# ECLOCK01.net
KiCad netlist of a schematic drawn in EAGLE
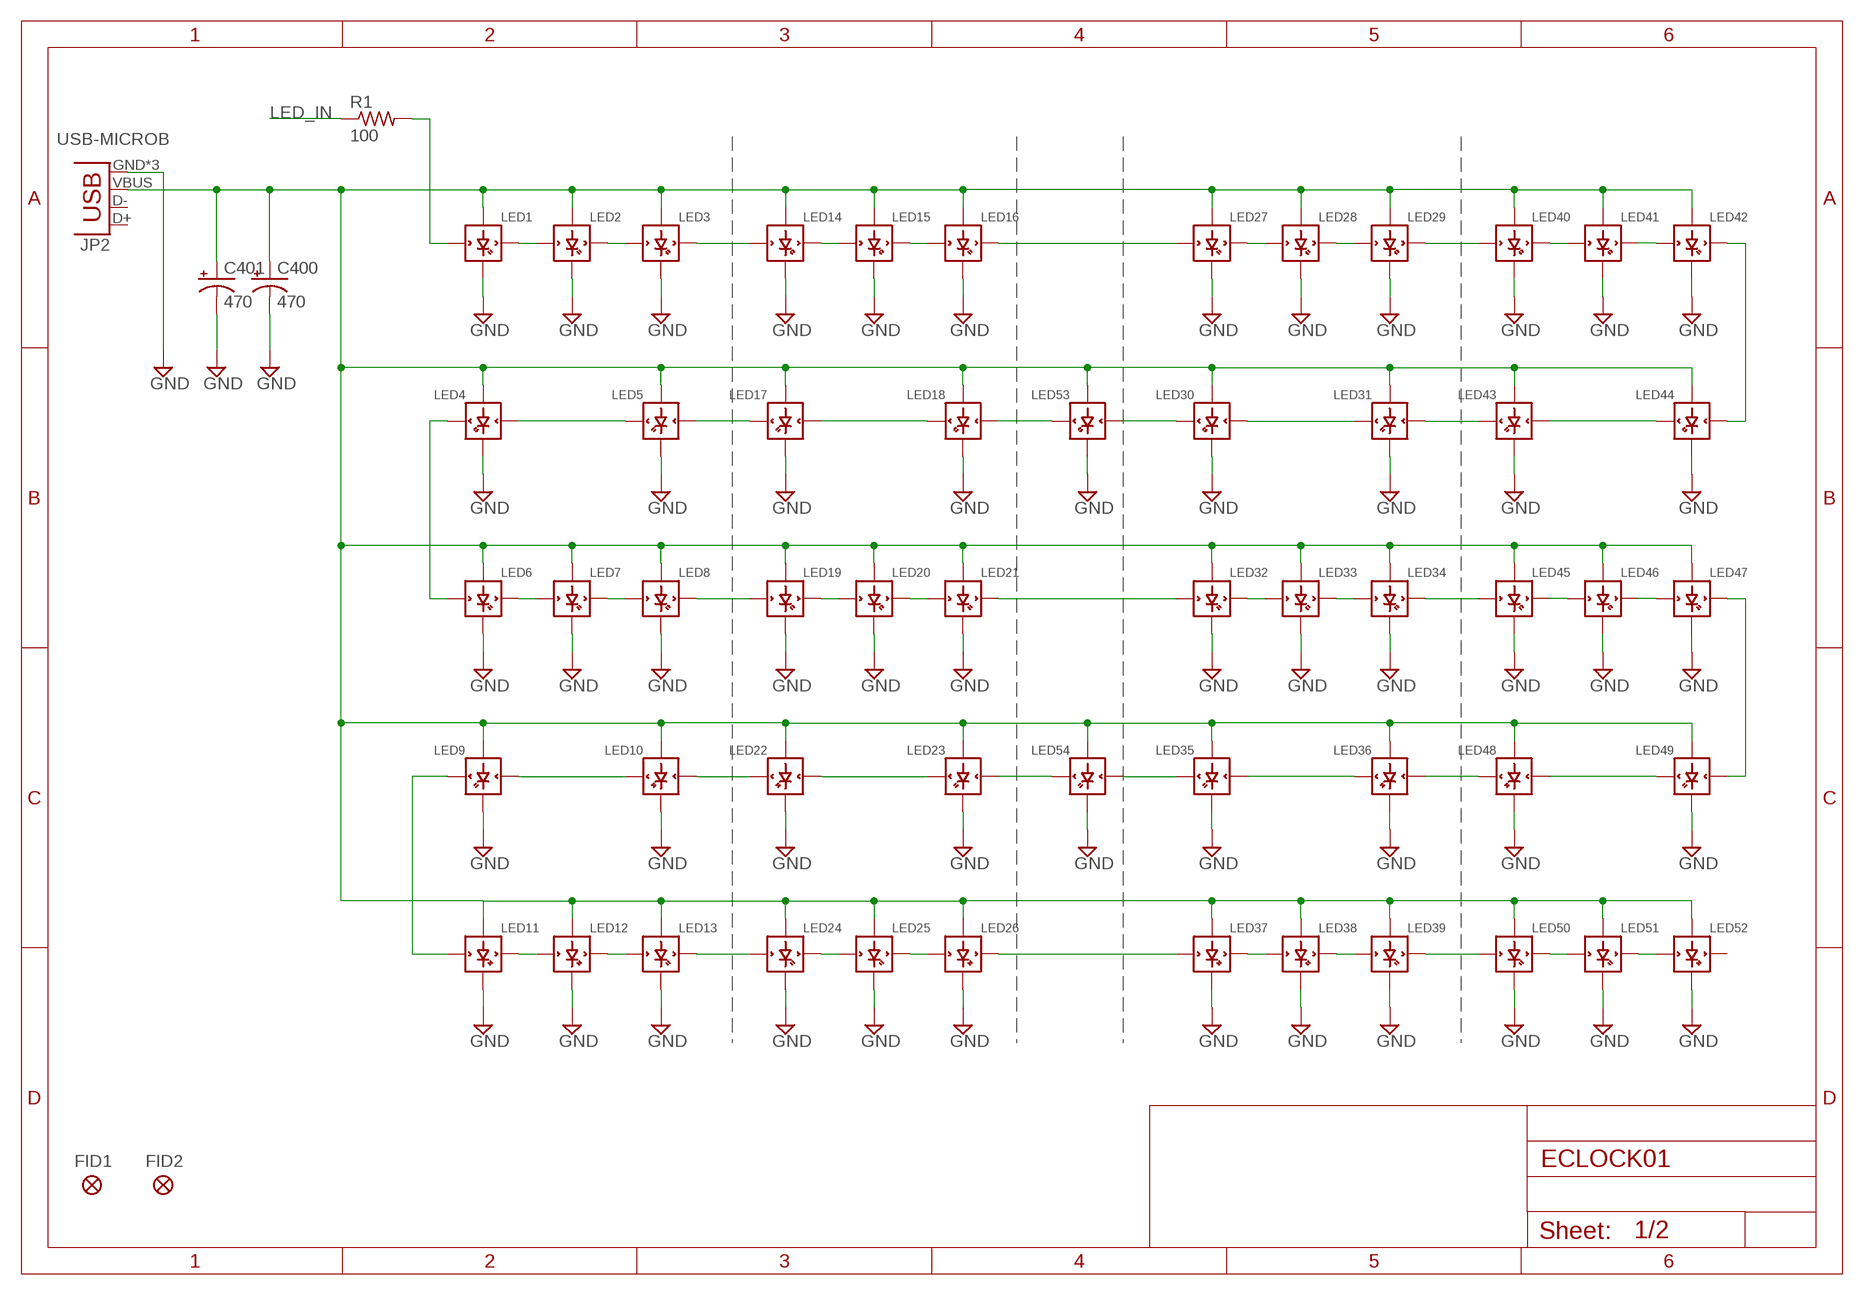
[diagram p0: schematic, sheet 1]
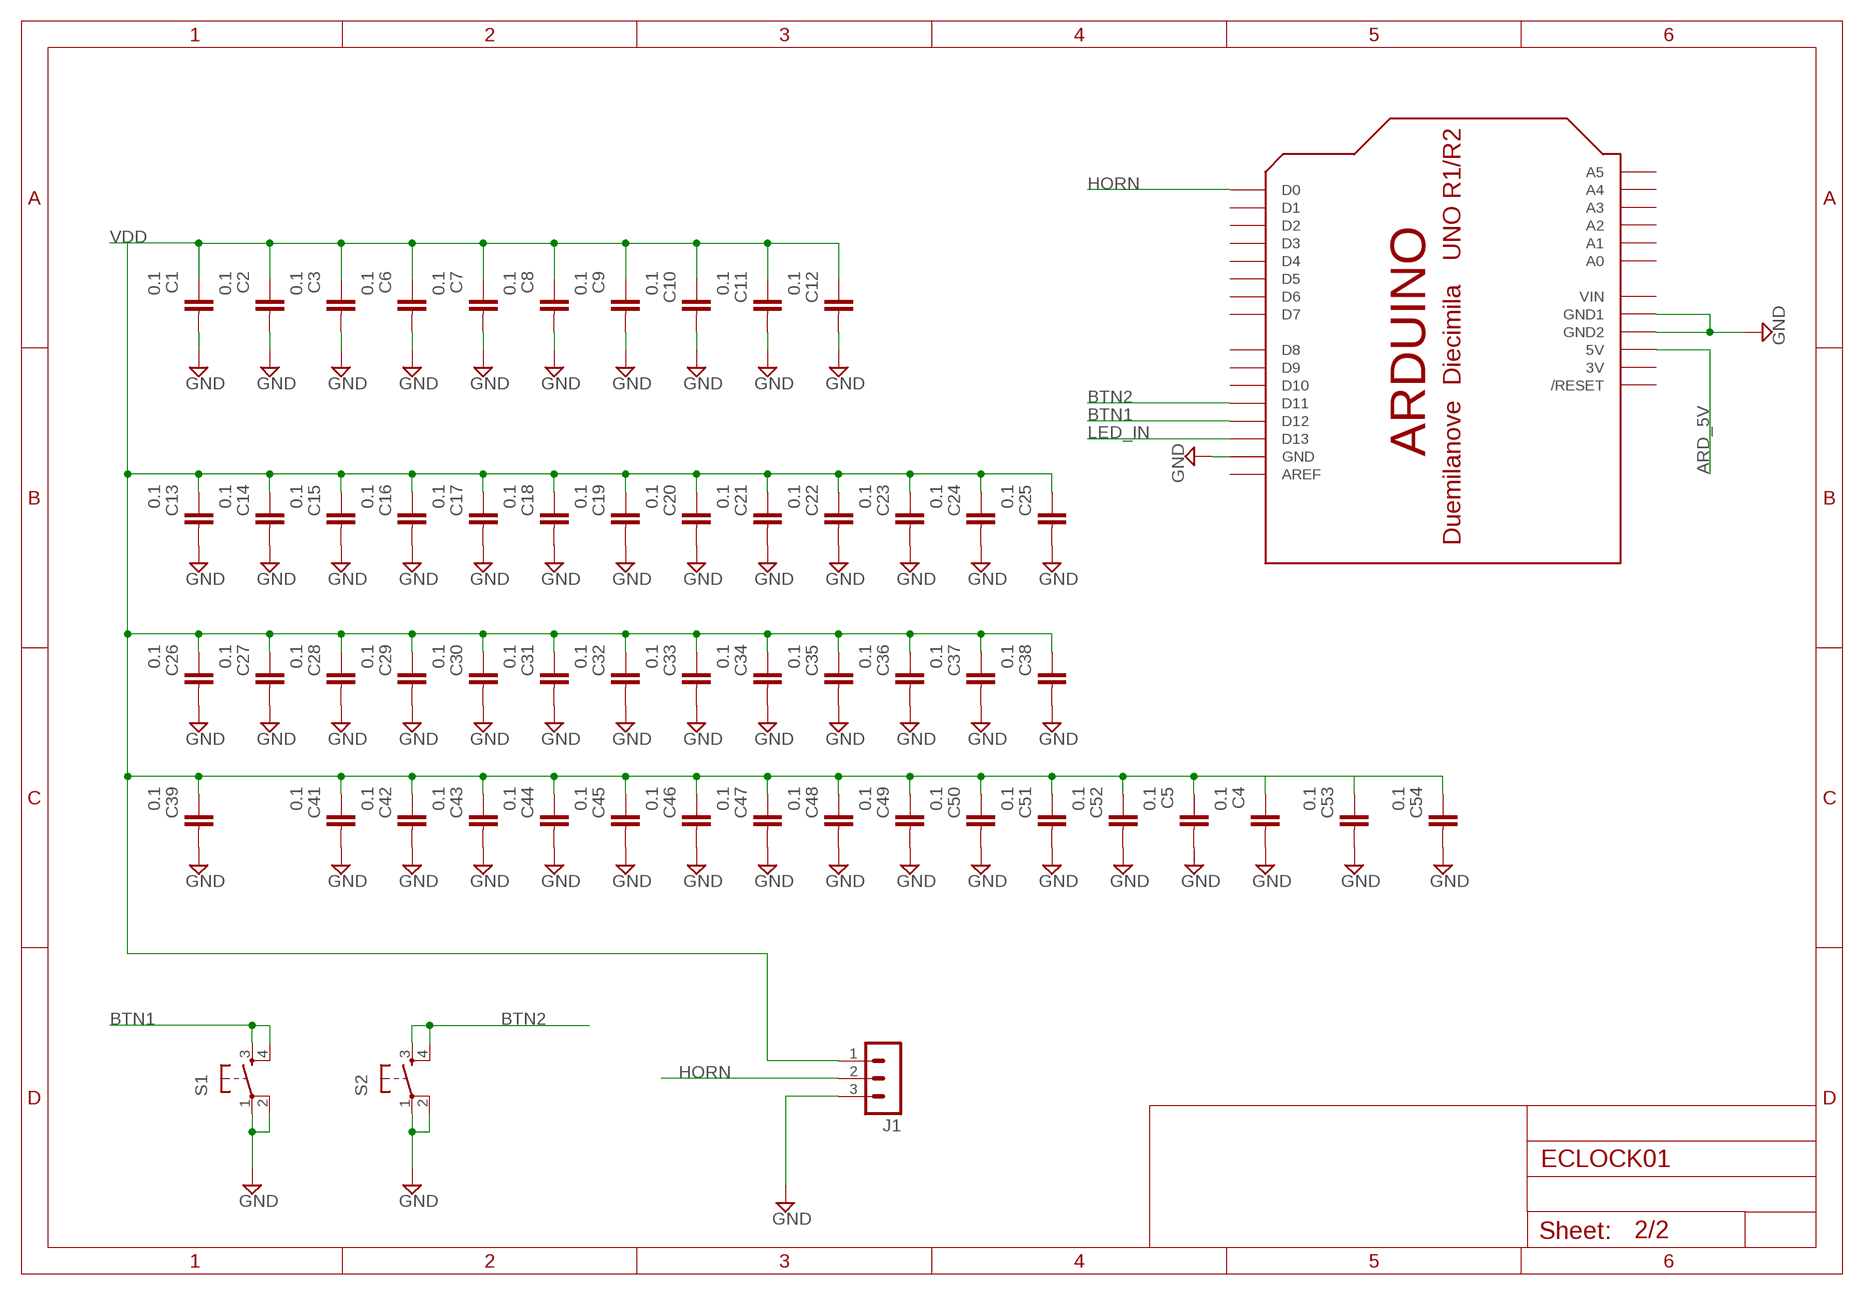
[diagram p1: schematic, sheet 2]

(export (version "E")
  (design (tool "Eeschema 10.0.6"))
  (components
    (comp (ref "C400")
      (value "470")
      (footprint "eagle-import:PANASONIC_E")
      (libsource (lib "eagle-import") (part "CPOL-USE"))
    )
    (comp (ref "C401")
      (value "470")
      (footprint "eagle-import:PANASONIC_E")
      (libsource (lib "eagle-import") (part "CPOL-USE"))
    )
    (comp (ref "FID1")
      (value "FIDUCIAL")
      (footprint "eagle-import:FIDUCIAL")
      (libsource (lib "eagle-import") (part "FIDUCIAL"))
    )
    (comp (ref "FID2")
      (value "FIDUCIAL")
      (footprint "eagle-import:FIDUCIAL")
      (libsource (lib "eagle-import") (part "FIDUCIAL"))
    )
    (comp (ref "JP2")
      (value "USB-MICROB")
      (footprint "eagle-import:USB-MICROB")
      (libsource (lib "eagle-import") (part "USB-MICROB"))
    )
    (comp (ref "LED1")
      (value "WS2812B")
      (footprint "eagle-import:WS2812B")
      (libsource (lib "eagle-import") (part "WS2812B"))
    )
    (comp (ref "LED2")
      (value "WS2812B")
      (footprint "eagle-import:WS2812B")
      (libsource (lib "eagle-import") (part "WS2812B"))
    )
    (comp (ref "LED3")
      (value "WS2812B")
      (footprint "eagle-import:WS2812B")
      (libsource (lib "eagle-import") (part "WS2812B"))
    )
    (comp (ref "LED4")
      (value "WS2812B")
      (footprint "eagle-import:WS2812B")
      (libsource (lib "eagle-import") (part "WS2812B"))
    )
    (comp (ref "LED5")
      (value "WS2812B")
      (footprint "eagle-import:WS2812B")
      (libsource (lib "eagle-import") (part "WS2812B"))
    )
    (comp (ref "LED6")
      (value "WS2812B")
      (footprint "eagle-import:WS2812B")
      (libsource (lib "eagle-import") (part "WS2812B"))
    )
    (comp (ref "LED7")
      (value "WS2812B")
      (footprint "eagle-import:WS2812B")
      (libsource (lib "eagle-import") (part "WS2812B"))
    )
    (comp (ref "LED8")
      (value "WS2812B")
      (footprint "eagle-import:WS2812B")
      (libsource (lib "eagle-import") (part "WS2812B"))
    )
    (comp (ref "LED9")
      (value "WS2812B")
      (footprint "eagle-import:WS2812B")
      (libsource (lib "eagle-import") (part "WS2812B"))
    )
    (comp (ref "LED10")
      (value "WS2812B")
      (footprint "eagle-import:WS2812B")
      (libsource (lib "eagle-import") (part "WS2812B"))
    )
    (comp (ref "LED11")
      (value "WS2812B")
      (footprint "eagle-import:WS2812B")
      (libsource (lib "eagle-import") (part "WS2812B"))
    )
    (comp (ref "LED12")
      (value "WS2812B")
      (footprint "eagle-import:WS2812B")
      (libsource (lib "eagle-import") (part "WS2812B"))
    )
    (comp (ref "LED13")
      (value "WS2812B")
      (footprint "eagle-import:WS2812B")
      (libsource (lib "eagle-import") (part "WS2812B"))
    )
    (comp (ref "LED14")
      (value "WS2812B")
      (footprint "eagle-import:WS2812B")
      (libsource (lib "eagle-import") (part "WS2812B"))
    )
    (comp (ref "LED15")
      (value "WS2812B")
      (footprint "eagle-import:WS2812B")
      (libsource (lib "eagle-import") (part "WS2812B"))
    )
    (comp (ref "LED16")
      (value "WS2812B")
      (footprint "eagle-import:WS2812B")
      (libsource (lib "eagle-import") (part "WS2812B"))
    )
    (comp (ref "LED17")
      (value "WS2812B")
      (footprint "eagle-import:WS2812B")
      (libsource (lib "eagle-import") (part "WS2812B"))
    )
    (comp (ref "LED18")
      (value "WS2812B")
      (footprint "eagle-import:WS2812B")
      (libsource (lib "eagle-import") (part "WS2812B"))
    )
    (comp (ref "LED19")
      (value "WS2812B")
      (footprint "eagle-import:WS2812B")
      (libsource (lib "eagle-import") (part "WS2812B"))
    )
    (comp (ref "LED20")
      (value "WS2812B")
      (footprint "eagle-import:WS2812B")
      (libsource (lib "eagle-import") (part "WS2812B"))
    )
    (comp (ref "LED21")
      (value "WS2812B")
      (footprint "eagle-import:WS2812B")
      (libsource (lib "eagle-import") (part "WS2812B"))
    )
    (comp (ref "LED22")
      (value "WS2812B")
      (footprint "eagle-import:WS2812B")
      (libsource (lib "eagle-import") (part "WS2812B"))
    )
    (comp (ref "LED23")
      (value "WS2812B")
      (footprint "eagle-import:WS2812B")
      (libsource (lib "eagle-import") (part "WS2812B"))
    )
    (comp (ref "LED24")
      (value "WS2812B")
      (footprint "eagle-import:WS2812B")
      (libsource (lib "eagle-import") (part "WS2812B"))
    )
    (comp (ref "LED25")
      (value "WS2812B")
      (footprint "eagle-import:WS2812B")
      (libsource (lib "eagle-import") (part "WS2812B"))
    )
    (comp (ref "LED26")
      (value "WS2812B")
      (footprint "eagle-import:WS2812B")
      (libsource (lib "eagle-import") (part "WS2812B"))
    )
    (comp (ref "LED27")
      (value "WS2812B")
      (footprint "eagle-import:WS2812B")
      (libsource (lib "eagle-import") (part "WS2812B"))
    )
    (comp (ref "LED28")
      (value "WS2812B")
      (footprint "eagle-import:WS2812B")
      (libsource (lib "eagle-import") (part "WS2812B"))
    )
    (comp (ref "LED29")
      (value "WS2812B")
      (footprint "eagle-import:WS2812B")
      (libsource (lib "eagle-import") (part "WS2812B"))
    )
    (comp (ref "LED30")
      (value "WS2812B")
      (footprint "eagle-import:WS2812B")
      (libsource (lib "eagle-import") (part "WS2812B"))
    )
    (comp (ref "LED31")
      (value "WS2812B")
      (footprint "eagle-import:WS2812B")
      (libsource (lib "eagle-import") (part "WS2812B"))
    )
    (comp (ref "LED32")
      (value "WS2812B")
      (footprint "eagle-import:WS2812B")
      (libsource (lib "eagle-import") (part "WS2812B"))
    )
    (comp (ref "LED33")
      (value "WS2812B")
      (footprint "eagle-import:WS2812B")
      (libsource (lib "eagle-import") (part "WS2812B"))
    )
    (comp (ref "LED34")
      (value "WS2812B")
      (footprint "eagle-import:WS2812B")
      (libsource (lib "eagle-import") (part "WS2812B"))
    )
    (comp (ref "LED35")
      (value "WS2812B")
      (footprint "eagle-import:WS2812B")
      (libsource (lib "eagle-import") (part "WS2812B"))
    )
    (comp (ref "LED36")
      (value "WS2812B")
      (footprint "eagle-import:WS2812B")
      (libsource (lib "eagle-import") (part "WS2812B"))
    )
    (comp (ref "LED37")
      (value "WS2812B")
      (footprint "eagle-import:WS2812B")
      (libsource (lib "eagle-import") (part "WS2812B"))
    )
    (comp (ref "LED38")
      (value "WS2812B")
      (footprint "eagle-import:WS2812B")
      (libsource (lib "eagle-import") (part "WS2812B"))
    )
    (comp (ref "LED39")
      (value "WS2812B")
      (footprint "eagle-import:WS2812B")
      (libsource (lib "eagle-import") (part "WS2812B"))
    )
    (comp (ref "LED40")
      (value "WS2812B")
      (footprint "eagle-import:WS2812B")
      (libsource (lib "eagle-import") (part "WS2812B"))
    )
    (comp (ref "LED41")
      (value "WS2812B")
      (footprint "eagle-import:WS2812B")
      (libsource (lib "eagle-import") (part "WS2812B"))
    )
    (comp (ref "LED42")
      (value "WS2812B")
      (footprint "eagle-import:WS2812B")
      (libsource (lib "eagle-import") (part "WS2812B"))
    )
    (comp (ref "LED43")
      (value "WS2812B")
      (footprint "eagle-import:WS2812B")
      (libsource (lib "eagle-import") (part "WS2812B"))
    )
    (comp (ref "LED44")
      (value "WS2812B")
      (footprint "eagle-import:WS2812B")
      (libsource (lib "eagle-import") (part "WS2812B"))
    )
    (comp (ref "LED45")
      (value "WS2812B")
      (footprint "eagle-import:WS2812B")
      (libsource (lib "eagle-import") (part "WS2812B"))
    )
    (comp (ref "LED46")
      (value "WS2812B")
      (footprint "eagle-import:WS2812B")
      (libsource (lib "eagle-import") (part "WS2812B"))
    )
    (comp (ref "LED47")
      (value "WS2812B")
      (footprint "eagle-import:WS2812B")
      (libsource (lib "eagle-import") (part "WS2812B"))
    )
    (comp (ref "LED48")
      (value "WS2812B")
      (footprint "eagle-import:WS2812B")
      (libsource (lib "eagle-import") (part "WS2812B"))
    )
    (comp (ref "LED49")
      (value "WS2812B")
      (footprint "eagle-import:WS2812B")
      (libsource (lib "eagle-import") (part "WS2812B"))
    )
    (comp (ref "LED50")
      (value "WS2812B")
      (footprint "eagle-import:WS2812B")
      (libsource (lib "eagle-import") (part "WS2812B"))
    )
    (comp (ref "LED51")
      (value "WS2812B")
      (footprint "eagle-import:WS2812B")
      (libsource (lib "eagle-import") (part "WS2812B"))
    )
    (comp (ref "LED52")
      (value "WS2812B")
      (footprint "eagle-import:WS2812B")
      (libsource (lib "eagle-import") (part "WS2812B"))
    )
    (comp (ref "LED53")
      (value "WS2812B")
      (footprint "eagle-import:WS2812B")
      (libsource (lib "eagle-import") (part "WS2812B"))
    )
    (comp (ref "LED54")
      (value "WS2812B")
      (footprint "eagle-import:WS2812B")
      (libsource (lib "eagle-import") (part "WS2812B"))
    )
    (comp (ref "R1")
      (value "100")
      (footprint "eagle-import:0805")
      (libsource (lib "eagle-import") (part "RESISTOR0805"))
    )
    (comp (ref "C1")
      (value "0.1")
      (footprint "eagle-import:0805")
      (libsource (lib "eagle-import") (part "CAPACITOR0805"))
    )
    (comp (ref "C2")
      (value "0.1")
      (footprint "eagle-import:0805")
      (libsource (lib "eagle-import") (part "CAPACITOR0805"))
    )
    (comp (ref "C3")
      (value "0.1")
      (footprint "eagle-import:0805")
      (libsource (lib "eagle-import") (part "CAPACITOR0805"))
    )
    (comp (ref "C4")
      (value "0.1")
      (footprint "eagle-import:0805")
      (libsource (lib "eagle-import") (part "CAPACITOR0805"))
    )
    (comp (ref "C5")
      (value "0.1")
      (footprint "eagle-import:0805")
      (libsource (lib "eagle-import") (part "CAPACITOR0805"))
    )
    (comp (ref "C6")
      (value "0.1")
      (footprint "eagle-import:0805")
      (libsource (lib "eagle-import") (part "CAPACITOR0805"))
    )
    (comp (ref "C7")
      (value "0.1")
      (footprint "eagle-import:0805")
      (libsource (lib "eagle-import") (part "CAPACITOR0805"))
    )
    (comp (ref "C8")
      (value "0.1")
      (footprint "eagle-import:0805")
      (libsource (lib "eagle-import") (part "CAPACITOR0805"))
    )
    (comp (ref "C9")
      (value "0.1")
      (footprint "eagle-import:0805")
      (libsource (lib "eagle-import") (part "CAPACITOR0805"))
    )
    (comp (ref "C10")
      (value "0.1")
      (footprint "eagle-import:0805")
      (libsource (lib "eagle-import") (part "CAPACITOR0805"))
    )
    (comp (ref "C11")
      (value "0.1")
      (footprint "eagle-import:0805")
      (libsource (lib "eagle-import") (part "CAPACITOR0805"))
    )
    (comp (ref "C12")
      (value "0.1")
      (footprint "eagle-import:0805")
      (libsource (lib "eagle-import") (part "CAPACITOR0805"))
    )
    (comp (ref "C13")
      (value "0.1")
      (footprint "eagle-import:0805")
      (libsource (lib "eagle-import") (part "CAPACITOR0805"))
    )
    (comp (ref "C14")
      (value "0.1")
      (footprint "eagle-import:0805")
      (libsource (lib "eagle-import") (part "CAPACITOR0805"))
    )
    (comp (ref "C15")
      (value "0.1")
      (footprint "eagle-import:0805")
      (libsource (lib "eagle-import") (part "CAPACITOR0805"))
    )
    (comp (ref "C16")
      (value "0.1")
      (footprint "eagle-import:0805")
      (libsource (lib "eagle-import") (part "CAPACITOR0805"))
    )
    (comp (ref "C17")
      (value "0.1")
      (footprint "eagle-import:0805")
      (libsource (lib "eagle-import") (part "CAPACITOR0805"))
    )
    (comp (ref "C18")
      (value "0.1")
      (footprint "eagle-import:0805")
      (libsource (lib "eagle-import") (part "CAPACITOR0805"))
    )
    (comp (ref "C19")
      (value "0.1")
      (footprint "eagle-import:0805")
      (libsource (lib "eagle-import") (part "CAPACITOR0805"))
    )
    (comp (ref "C20")
      (value "0.1")
      (footprint "eagle-import:0805")
      (libsource (lib "eagle-import") (part "CAPACITOR0805"))
    )
    (comp (ref "C21")
      (value "0.1")
      (footprint "eagle-import:0805")
      (libsource (lib "eagle-import") (part "CAPACITOR0805"))
    )
    (comp (ref "C22")
      (value "0.1")
      (footprint "eagle-import:0805")
      (libsource (lib "eagle-import") (part "CAPACITOR0805"))
    )
    (comp (ref "C23")
      (value "0.1")
      (footprint "eagle-import:0805")
      (libsource (lib "eagle-import") (part "CAPACITOR0805"))
    )
    (comp (ref "C24")
      (value "0.1")
      (footprint "eagle-import:0805")
      (libsource (lib "eagle-import") (part "CAPACITOR0805"))
    )
    (comp (ref "C25")
      (value "0.1")
      (footprint "eagle-import:0805")
      (libsource (lib "eagle-import") (part "CAPACITOR0805"))
    )
    (comp (ref "C26")
      (value "0.1")
      (footprint "eagle-import:0805")
      (libsource (lib "eagle-import") (part "CAPACITOR0805"))
    )
    (comp (ref "C27")
      (value "0.1")
      (footprint "eagle-import:0805")
      (libsource (lib "eagle-import") (part "CAPACITOR0805"))
    )
    (comp (ref "C28")
      (value "0.1")
      (footprint "eagle-import:0805")
      (libsource (lib "eagle-import") (part "CAPACITOR0805"))
    )
    (comp (ref "C29")
      (value "0.1")
      (footprint "eagle-import:0805")
      (libsource (lib "eagle-import") (part "CAPACITOR0805"))
    )
    (comp (ref "C30")
      (value "0.1")
      (footprint "eagle-import:0805")
      (libsource (lib "eagle-import") (part "CAPACITOR0805"))
    )
    (comp (ref "C31")
      (value "0.1")
      (footprint "eagle-import:0805")
      (libsource (lib "eagle-import") (part "CAPACITOR0805"))
    )
    (comp (ref "C32")
      (value "0.1")
      (footprint "eagle-import:0805")
      (libsource (lib "eagle-import") (part "CAPACITOR0805"))
    )
    (comp (ref "C33")
      (value "0.1")
      (footprint "eagle-import:0805")
      (libsource (lib "eagle-import") (part "CAPACITOR0805"))
    )
    (comp (ref "C34")
      (value "0.1")
      (footprint "eagle-import:0805")
      (libsource (lib "eagle-import") (part "CAPACITOR0805"))
    )
    (comp (ref "C35")
      (value "0.1")
      (footprint "eagle-import:0805")
      (libsource (lib "eagle-import") (part "CAPACITOR0805"))
    )
    (comp (ref "C36")
      (value "0.1")
      (footprint "eagle-import:0805")
      (libsource (lib "eagle-import") (part "CAPACITOR0805"))
    )
    (comp (ref "C37")
      (value "0.1")
      (footprint "eagle-import:0805")
      (libsource (lib "eagle-import") (part "CAPACITOR0805"))
    )
    (comp (ref "C38")
      (value "0.1")
      (footprint "eagle-import:0805")
      (libsource (lib "eagle-import") (part "CAPACITOR0805"))
    )
    (comp (ref "C39")
      (value "0.1")
      (footprint "eagle-import:0805")
      (libsource (lib "eagle-import") (part "CAPACITOR0805"))
    )
    (comp (ref "C41")
      (value "0.1")
      (footprint "eagle-import:0805")
      (libsource (lib "eagle-import") (part "CAPACITOR0805"))
    )
    (comp (ref "C42")
      (value "0.1")
      (footprint "eagle-import:0805")
      (libsource (lib "eagle-import") (part "CAPACITOR0805"))
    )
    (comp (ref "C43")
      (value "0.1")
      (footprint "eagle-import:0805")
      (libsource (lib "eagle-import") (part "CAPACITOR0805"))
    )
    (comp (ref "C44")
      (value "0.1")
      (footprint "eagle-import:0805")
      (libsource (lib "eagle-import") (part "CAPACITOR0805"))
    )
    (comp (ref "C45")
      (value "0.1")
      (footprint "eagle-import:0805")
      (libsource (lib "eagle-import") (part "CAPACITOR0805"))
    )
    (comp (ref "C46")
      (value "0.1")
      (footprint "eagle-import:0805")
      (libsource (lib "eagle-import") (part "CAPACITOR0805"))
    )
    (comp (ref "C47")
      (value "0.1")
      (footprint "eagle-import:0805")
      (libsource (lib "eagle-import") (part "CAPACITOR0805"))
    )
    (comp (ref "C48")
      (value "0.1")
      (footprint "eagle-import:0805")
      (libsource (lib "eagle-import") (part "CAPACITOR0805"))
    )
    (comp (ref "C49")
      (value "0.1")
      (footprint "eagle-import:0805")
      (libsource (lib "eagle-import") (part "CAPACITOR0805"))
    )
    (comp (ref "C50")
      (value "0.1")
      (footprint "eagle-import:0805")
      (libsource (lib "eagle-import") (part "CAPACITOR0805"))
    )
    (comp (ref "C51")
      (value "0.1")
      (footprint "eagle-import:0805")
      (libsource (lib "eagle-import") (part "CAPACITOR0805"))
    )
    (comp (ref "C52")
      (value "0.1")
      (footprint "eagle-import:0805")
      (libsource (lib "eagle-import") (part "CAPACITOR0805"))
    )
    (comp (ref "C53")
      (value "0.1")
      (footprint "eagle-import:0805")
      (libsource (lib "eagle-import") (part "CAPACITOR0805"))
    )
    (comp (ref "C54")
      (value "0.1")
      (footprint "eagle-import:0805")
      (libsource (lib "eagle-import") (part "CAPACITOR0805"))
    )
    (comp (ref "J1")
      (value "MA03-1")
      (footprint "eagle-import:MA03-1")
      (libsource (lib "eagle-import") (part "MA03-1"))
    )
    (comp (ref "S1")
      (value "TAC_SWITCHSMD")
      (footprint "eagle-import:TACTILE_SWITCH_SMD")
      (libsource (lib "eagle-import") (part "TAC_SWITCHSMD"))
    )
    (comp (ref "S2")
      (value "TAC_SWITCHSMD")
      (footprint "eagle-import:TACTILE_SWITCH_SMD")
      (libsource (lib "eagle-import") (part "TAC_SWITCHSMD"))
    )
    (comp (ref "U$1")
      (value "ARDUINOUNO")
      (footprint "eagle-import:ARDUINO-UNO")
      (libsource (lib "eagle-import") (part "ARDUINOUNO"))
    )
  )
  (nets
    (net (code "1") (name "3V") (class "Default")
      (node (ref "U$1") (pin "3V") (pinfunction "3V_3V") (pintype "power_in"))
    )
    (net (code "2") (name "ARD_5V") (class "Default")
      (node (ref "U$1") (pin "5V") (pinfunction "5V_5V") (pintype "power_in"))
    )
    (net (code "3") (name "BTN1") (class "Default")
      (node (ref "S1") (pin "3") (pinfunction "3_3") (pintype "passive"))
      (node (ref "S1") (pin "4") (pinfunction "4_4") (pintype "passive"))
      (node (ref "U$1") (pin "D12") (pinfunction "D12_D12") (pintype "bidirectional"))
    )
    (net (code "4") (name "BTN2") (class "Default")
      (node (ref "S2") (pin "3") (pinfunction "3_3") (pintype "passive"))
      (node (ref "S2") (pin "4") (pinfunction "4_4") (pintype "passive"))
      (node (ref "U$1") (pin "D11") (pinfunction "D11_D11") (pintype "bidirectional"))
    )
    (net (code "5") (name "GND") (class "Default")
      (node (ref "C1") (pin "2") (pinfunction "2_2") (pintype "passive"))
      (node (ref "C10") (pin "2") (pinfunction "2_2") (pintype "passive"))
      (node (ref "C11") (pin "2") (pinfunction "2_2") (pintype "passive"))
      (node (ref "C12") (pin "2") (pinfunction "2_2") (pintype "passive"))
      (node (ref "C13") (pin "2") (pinfunction "2_2") (pintype "passive"))
      (node (ref "C14") (pin "2") (pinfunction "2_2") (pintype "passive"))
      (node (ref "C15") (pin "2") (pinfunction "2_2") (pintype "passive"))
      (node (ref "C16") (pin "2") (pinfunction "2_2") (pintype "passive"))
      (node (ref "C17") (pin "2") (pinfunction "2_2") (pintype "passive"))
      (node (ref "C18") (pin "2") (pinfunction "2_2") (pintype "passive"))
      (node (ref "C19") (pin "2") (pinfunction "2_2") (pintype "passive"))
      (node (ref "C2") (pin "2") (pinfunction "2_2") (pintype "passive"))
      (node (ref "C20") (pin "2") (pinfunction "2_2") (pintype "passive"))
      (node (ref "C21") (pin "2") (pinfunction "2_2") (pintype "passive"))
      (node (ref "C22") (pin "2") (pinfunction "2_2") (pintype "passive"))
      (node (ref "C23") (pin "2") (pinfunction "2_2") (pintype "passive"))
      (node (ref "C24") (pin "2") (pinfunction "2_2") (pintype "passive"))
      (node (ref "C25") (pin "2") (pinfunction "2_2") (pintype "passive"))
      (node (ref "C26") (pin "2") (pinfunction "2_2") (pintype "passive"))
      (node (ref "C27") (pin "2") (pinfunction "2_2") (pintype "passive"))
      (node (ref "C28") (pin "2") (pinfunction "2_2") (pintype "passive"))
      (node (ref "C29") (pin "2") (pinfunction "2_2") (pintype "passive"))
      (node (ref "C3") (pin "2") (pinfunction "2_2") (pintype "passive"))
      (node (ref "C30") (pin "2") (pinfunction "2_2") (pintype "passive"))
      (node (ref "C31") (pin "2") (pinfunction "2_2") (pintype "passive"))
      (node (ref "C32") (pin "2") (pinfunction "2_2") (pintype "passive"))
      (node (ref "C33") (pin "2") (pinfunction "2_2") (pintype "passive"))
      (node (ref "C34") (pin "2") (pinfunction "2_2") (pintype "passive"))
      (node (ref "C35") (pin "2") (pinfunction "2_2") (pintype "passive"))
      (node (ref "C36") (pin "2") (pinfunction "2_2") (pintype "passive"))
      (node (ref "C37") (pin "2") (pinfunction "2_2") (pintype "passive"))
      (node (ref "C38") (pin "2") (pinfunction "2_2") (pintype "passive"))
      (node (ref "C39") (pin "2") (pinfunction "2_2") (pintype "passive"))
      (node (ref "C4") (pin "2") (pinfunction "2_2") (pintype "passive"))
      (node (ref "C400") (pin "-") (pinfunction "-_-") (pintype "passive"))
      (node (ref "C401") (pin "-") (pinfunction "-_-") (pintype "passive"))
      (node (ref "C41") (pin "2") (pinfunction "2_2") (pintype "passive"))
      (node (ref "C42") (pin "2") (pinfunction "2_2") (pintype "passive"))
      (node (ref "C43") (pin "2") (pinfunction "2_2") (pintype "passive"))
      (node (ref "C44") (pin "2") (pinfunction "2_2") (pintype "passive"))
      (node (ref "C45") (pin "2") (pinfunction "2_2") (pintype "passive"))
      (node (ref "C46") (pin "2") (pinfunction "2_2") (pintype "passive"))
      (node (ref "C47") (pin "2") (pinfunction "2_2") (pintype "passive"))
      (node (ref "C48") (pin "2") (pinfunction "2_2") (pintype "passive"))
      (node (ref "C49") (pin "2") (pinfunction "2_2") (pintype "passive"))
      (node (ref "C5") (pin "2") (pinfunction "2_2") (pintype "passive"))
      (node (ref "C50") (pin "2") (pinfunction "2_2") (pintype "passive"))
      (node (ref "C51") (pin "2") (pinfunction "2_2") (pintype "passive"))
      (node (ref "C52") (pin "2") (pinfunction "2_2") (pintype "passive"))
      (node (ref "C53") (pin "2") (pinfunction "2_2") (pintype "passive"))
      (node (ref "C54") (pin "2") (pinfunction "2_2") (pintype "passive"))
      (node (ref "C6") (pin "2") (pinfunction "2_2") (pintype "passive"))
      (node (ref "C7") (pin "2") (pinfunction "2_2") (pintype "passive"))
      (node (ref "C8") (pin "2") (pinfunction "2_2") (pintype "passive"))
      (node (ref "C9") (pin "2") (pinfunction "2_2") (pintype "passive"))
      (node (ref "J1") (pin "3") (pinfunction "3_3") (pintype "passive"))
      (node (ref "JP2") (pin "GND") (pinfunction "GND_GND") (pintype "bidirectional"))
      (node (ref "JP2") (pin "MT1") (pinfunction "GND_MT1") (pintype "bidirectional"))
      (node (ref "JP2") (pin "MT2") (pinfunction "GND_MT2") (pintype "bidirectional"))
      (node (ref "LED1") (pin "3-GND") (pinfunction "GND_3-GND") (pintype "bidirectional"))
      (node (ref "LED10") (pin "3-GND") (pinfunction "GND_3-GND") (pintype "bidirectional"))
      (node (ref "LED11") (pin "3-GND") (pinfunction "GND_3-GND") (pintype "bidirectional"))
      (node (ref "LED12") (pin "3-GND") (pinfunction "GND_3-GND") (pintype "bidirectional"))
      (node (ref "LED13") (pin "3-GND") (pinfunction "GND_3-GND") (pintype "bidirectional"))
      (node (ref "LED14") (pin "3-GND") (pinfunction "GND_3-GND") (pintype "bidirectional"))
      (node (ref "LED15") (pin "3-GND") (pinfunction "GND_3-GND") (pintype "bidirectional"))
      (node (ref "LED16") (pin "3-GND") (pinfunction "GND_3-GND") (pintype "bidirectional"))
      (node (ref "LED17") (pin "3-GND") (pinfunction "GND_3-GND") (pintype "bidirectional"))
      (node (ref "LED18") (pin "3-GND") (pinfunction "GND_3-GND") (pintype "bidirectional"))
      (node (ref "LED19") (pin "3-GND") (pinfunction "GND_3-GND") (pintype "bidirectional"))
      (node (ref "LED2") (pin "3-GND") (pinfunction "GND_3-GND") (pintype "bidirectional"))
      (node (ref "LED20") (pin "3-GND") (pinfunction "GND_3-GND") (pintype "bidirectional"))
      (node (ref "LED21") (pin "3-GND") (pinfunction "GND_3-GND") (pintype "bidirectional"))
      (node (ref "LED22") (pin "3-GND") (pinfunction "GND_3-GND") (pintype "bidirectional"))
      (node (ref "LED23") (pin "3-GND") (pinfunction "GND_3-GND") (pintype "bidirectional"))
      (node (ref "LED24") (pin "3-GND") (pinfunction "GND_3-GND") (pintype "bidirectional"))
      (node (ref "LED25") (pin "3-GND") (pinfunction "GND_3-GND") (pintype "bidirectional"))
      (node (ref "LED26") (pin "3-GND") (pinfunction "GND_3-GND") (pintype "bidirectional"))
      (node (ref "LED27") (pin "3-GND") (pinfunction "GND_3-GND") (pintype "bidirectional"))
      (node (ref "LED28") (pin "3-GND") (pinfunction "GND_3-GND") (pintype "bidirectional"))
      (node (ref "LED29") (pin "3-GND") (pinfunction "GND_3-GND") (pintype "bidirectional"))
      (node (ref "LED3") (pin "3-GND") (pinfunction "GND_3-GND") (pintype "bidirectional"))
      (node (ref "LED30") (pin "3-GND") (pinfunction "GND_3-GND") (pintype "bidirectional"))
      (node (ref "LED31") (pin "3-GND") (pinfunction "GND_3-GND") (pintype "bidirectional"))
      (node (ref "LED32") (pin "3-GND") (pinfunction "GND_3-GND") (pintype "bidirectional"))
      (node (ref "LED33") (pin "3-GND") (pinfunction "GND_3-GND") (pintype "bidirectional"))
      (node (ref "LED34") (pin "3-GND") (pinfunction "GND_3-GND") (pintype "bidirectional"))
      (node (ref "LED35") (pin "3-GND") (pinfunction "GND_3-GND") (pintype "bidirectional"))
      (node (ref "LED36") (pin "3-GND") (pinfunction "GND_3-GND") (pintype "bidirectional"))
      (node (ref "LED37") (pin "3-GND") (pinfunction "GND_3-GND") (pintype "bidirectional"))
      (node (ref "LED38") (pin "3-GND") (pinfunction "GND_3-GND") (pintype "bidirectional"))
      (node (ref "LED39") (pin "3-GND") (pinfunction "GND_3-GND") (pintype "bidirectional"))
      (node (ref "LED4") (pin "3-GND") (pinfunction "GND_3-GND") (pintype "bidirectional"))
      (node (ref "LED40") (pin "3-GND") (pinfunction "GND_3-GND") (pintype "bidirectional"))
      (node (ref "LED41") (pin "3-GND") (pinfunction "GND_3-GND") (pintype "bidirectional"))
      (node (ref "LED42") (pin "3-GND") (pinfunction "GND_3-GND") (pintype "bidirectional"))
      (node (ref "LED43") (pin "3-GND") (pinfunction "GND_3-GND") (pintype "bidirectional"))
      (node (ref "LED44") (pin "3-GND") (pinfunction "GND_3-GND") (pintype "bidirectional"))
      (node (ref "LED45") (pin "3-GND") (pinfunction "GND_3-GND") (pintype "bidirectional"))
      (node (ref "LED46") (pin "3-GND") (pinfunction "GND_3-GND") (pintype "bidirectional"))
      (node (ref "LED47") (pin "3-GND") (pinfunction "GND_3-GND") (pintype "bidirectional"))
      (node (ref "LED48") (pin "3-GND") (pinfunction "GND_3-GND") (pintype "bidirectional"))
      (node (ref "LED49") (pin "3-GND") (pinfunction "GND_3-GND") (pintype "bidirectional"))
      (node (ref "LED5") (pin "3-GND") (pinfunction "GND_3-GND") (pintype "bidirectional"))
      (node (ref "LED50") (pin "3-GND") (pinfunction "GND_3-GND") (pintype "bidirectional"))
      (node (ref "LED51") (pin "3-GND") (pinfunction "GND_3-GND") (pintype "bidirectional"))
      (node (ref "LED52") (pin "3-GND") (pinfunction "GND_3-GND") (pintype "bidirectional"))
      (node (ref "LED53") (pin "3-GND") (pinfunction "GND_3-GND") (pintype "bidirectional"))
      (node (ref "LED54") (pin "3-GND") (pinfunction "GND_3-GND") (pintype "bidirectional"))
      (node (ref "LED6") (pin "3-GND") (pinfunction "GND_3-GND") (pintype "bidirectional"))
      (node (ref "LED7") (pin "3-GND") (pinfunction "GND_3-GND") (pintype "bidirectional"))
      (node (ref "LED8") (pin "3-GND") (pinfunction "GND_3-GND") (pintype "bidirectional"))
      (node (ref "LED9") (pin "3-GND") (pinfunction "GND_3-GND") (pintype "bidirectional"))
      (node (ref "S1") (pin "1") (pinfunction "1_1") (pintype "passive"))
      (node (ref "S1") (pin "2") (pinfunction "2_2") (pintype "passive"))
      (node (ref "S2") (pin "1") (pinfunction "1_1") (pintype "passive"))
      (node (ref "S2") (pin "2") (pinfunction "2_2") (pintype "passive"))
      (node (ref "U$1") (pin "GND") (pinfunction "GND_GND") (pintype "power_in"))
      (node (ref "U$1") (pin "GND1") (pinfunction "GND1_GND1") (pintype "power_in"))
      (node (ref "U$1") (pin "GND2") (pinfunction "GND2_GND2") (pintype "power_in"))
    )
    (net (code "6") (name "HORN") (class "Default")
      (node (ref "J1") (pin "2") (pinfunction "2_2") (pintype "passive"))
      (node (ref "U$1") (pin "D0") (pinfunction "D0_D0") (pintype "bidirectional"))
    )
    (net (code "7") (name "LED_IN") (class "Default")
      (node (ref "R1") (pin "1") (pinfunction "1_1") (pintype "passive"))
      (node (ref "U$1") (pin "D13") (pinfunction "D13_D13") (pintype "bidirectional"))
    )
    (net (code "8") (name "Net-(LED1-DIN)") (class "Default")
      (node (ref "LED1") (pin "4-DIN") (pinfunction "DIN_4-DIN") (pintype "input"))
      (node (ref "R1") (pin "2") (pinfunction "2_2") (pintype "passive"))
    )
    (net (code "9") (name "Net-(LED1-DOUT)") (class "Default")
      (node (ref "LED1") (pin "2-DOUT") (pinfunction "DOUT_2-DOUT") (pintype "output"))
      (node (ref "LED2") (pin "4-DIN") (pinfunction "DIN_4-DIN") (pintype "input"))
    )
    (net (code "10") (name "Net-(LED2-DOUT)") (class "Default")
      (node (ref "LED2") (pin "2-DOUT") (pinfunction "DOUT_2-DOUT") (pintype "output"))
      (node (ref "LED3") (pin "4-DIN") (pinfunction "DIN_4-DIN") (pintype "input"))
    )
    (net (code "11") (name "Net-(LED4-DIN)") (class "Default")
      (node (ref "LED4") (pin "4-DIN") (pinfunction "DIN_4-DIN") (pintype "input"))
      (node (ref "LED5") (pin "2-DOUT") (pinfunction "DOUT_2-DOUT") (pintype "output"))
    )
    (net (code "12") (name "Net-(LED4-DOUT)") (class "Default")
      (node (ref "LED4") (pin "2-DOUT") (pinfunction "DOUT_2-DOUT") (pintype "output"))
      (node (ref "LED6") (pin "4-DIN") (pinfunction "DIN_4-DIN") (pintype "input"))
    )
    (net (code "13") (name "Net-(LED6-DOUT)") (class "Default")
      (node (ref "LED6") (pin "2-DOUT") (pinfunction "DOUT_2-DOUT") (pintype "output"))
      (node (ref "LED7") (pin "4-DIN") (pinfunction "DIN_4-DIN") (pintype "input"))
    )
    (net (code "14") (name "Net-(LED7-DOUT)") (class "Default")
      (node (ref "LED7") (pin "2-DOUT") (pinfunction "DOUT_2-DOUT") (pintype "output"))
      (node (ref "LED8") (pin "4-DIN") (pinfunction "DIN_4-DIN") (pintype "input"))
    )
    (net (code "15") (name "Net-(LED10-DIN)") (class "Default")
      (node (ref "LED10") (pin "4-DIN") (pinfunction "DIN_4-DIN") (pintype "input"))
      (node (ref "LED22") (pin "2-DOUT") (pinfunction "DOUT_2-DOUT") (pintype "output"))
    )
    (net (code "16") (name "Net-(LED10-DOUT)") (class "Default")
      (node (ref "LED10") (pin "2-DOUT") (pinfunction "DOUT_2-DOUT") (pintype "output"))
      (node (ref "LED9") (pin "4-DIN") (pinfunction "DIN_4-DIN") (pintype "input"))
    )
    (net (code "17") (name "Net-(LED11-DIN)") (class "Default")
      (node (ref "LED11") (pin "4-DIN") (pinfunction "DIN_4-DIN") (pintype "input"))
      (node (ref "LED9") (pin "2-DOUT") (pinfunction "DOUT_2-DOUT") (pintype "output"))
    )
    (net (code "18") (name "Net-(LED11-DOUT)") (class "Default")
      (node (ref "LED11") (pin "2-DOUT") (pinfunction "DOUT_2-DOUT") (pintype "output"))
      (node (ref "LED12") (pin "4-DIN") (pinfunction "DIN_4-DIN") (pintype "input"))
    )
    (net (code "19") (name "Net-(LED12-DOUT)") (class "Default")
      (node (ref "LED12") (pin "2-DOUT") (pinfunction "DOUT_2-DOUT") (pintype "output"))
      (node (ref "LED13") (pin "4-DIN") (pinfunction "DIN_4-DIN") (pintype "input"))
    )
    (net (code "20") (name "Net-(LED13-DOUT)") (class "Default")
      (node (ref "LED13") (pin "2-DOUT") (pinfunction "DOUT_2-DOUT") (pintype "output"))
      (node (ref "LED24") (pin "4-DIN") (pinfunction "DIN_4-DIN") (pintype "input"))
    )
    (net (code "21") (name "Net-(LED14-DIN)") (class "Default")
      (node (ref "LED14") (pin "4-DIN") (pinfunction "DIN_4-DIN") (pintype "input"))
      (node (ref "LED3") (pin "2-DOUT") (pinfunction "DOUT_2-DOUT") (pintype "output"))
    )
    (net (code "22") (name "Net-(LED14-DOUT)") (class "Default")
      (node (ref "LED14") (pin "2-DOUT") (pinfunction "DOUT_2-DOUT") (pintype "output"))
      (node (ref "LED15") (pin "4-DIN") (pinfunction "DIN_4-DIN") (pintype "input"))
    )
    (net (code "23") (name "Net-(LED15-DOUT)") (class "Default")
      (node (ref "LED15") (pin "2-DOUT") (pinfunction "DOUT_2-DOUT") (pintype "output"))
      (node (ref "LED16") (pin "4-DIN") (pinfunction "DIN_4-DIN") (pintype "input"))
    )
    (net (code "24") (name "Net-(LED16-DOUT)") (class "Default")
      (node (ref "LED16") (pin "2-DOUT") (pinfunction "DOUT_2-DOUT") (pintype "output"))
      (node (ref "LED27") (pin "4-DIN") (pinfunction "DIN_4-DIN") (pintype "input"))
    )
    (net (code "25") (name "Net-(LED17-DIN)") (class "Default")
      (node (ref "LED17") (pin "4-DIN") (pinfunction "DIN_4-DIN") (pintype "input"))
      (node (ref "LED18") (pin "2-DOUT") (pinfunction "DOUT_2-DOUT") (pintype "output"))
    )
    (net (code "26") (name "Net-(LED17-DOUT)") (class "Default")
      (node (ref "LED17") (pin "2-DOUT") (pinfunction "DOUT_2-DOUT") (pintype "output"))
      (node (ref "LED5") (pin "4-DIN") (pinfunction "DIN_4-DIN") (pintype "input"))
    )
    (net (code "27") (name "Net-(LED18-DIN)") (class "Default")
      (node (ref "LED18") (pin "4-DIN") (pinfunction "DIN_4-DIN") (pintype "input"))
      (node (ref "LED53") (pin "2-DOUT") (pinfunction "DOUT_2-DOUT") (pintype "output"))
    )
    (net (code "28") (name "Net-(LED19-DIN)") (class "Default")
      (node (ref "LED19") (pin "4-DIN") (pinfunction "DIN_4-DIN") (pintype "input"))
      (node (ref "LED8") (pin "2-DOUT") (pinfunction "DOUT_2-DOUT") (pintype "output"))
    )
    (net (code "29") (name "Net-(LED19-DOUT)") (class "Default")
      (node (ref "LED19") (pin "2-DOUT") (pinfunction "DOUT_2-DOUT") (pintype "output"))
      (node (ref "LED20") (pin "4-DIN") (pinfunction "DIN_4-DIN") (pintype "input"))
    )
    (net (code "30") (name "Net-(LED20-DOUT)") (class "Default")
      (node (ref "LED20") (pin "2-DOUT") (pinfunction "DOUT_2-DOUT") (pintype "output"))
      (node (ref "LED21") (pin "4-DIN") (pinfunction "DIN_4-DIN") (pintype "input"))
    )
    (net (code "31") (name "Net-(LED21-DOUT)") (class "Default")
      (node (ref "LED21") (pin "2-DOUT") (pinfunction "DOUT_2-DOUT") (pintype "output"))
      (node (ref "LED32") (pin "4-DIN") (pinfunction "DIN_4-DIN") (pintype "input"))
    )
    (net (code "32") (name "Net-(LED22-DIN)") (class "Default")
      (node (ref "LED22") (pin "4-DIN") (pinfunction "DIN_4-DIN") (pintype "input"))
      (node (ref "LED23") (pin "2-DOUT") (pinfunction "DOUT_2-DOUT") (pintype "output"))
    )
    (net (code "33") (name "Net-(LED23-DIN)") (class "Default")
      (node (ref "LED23") (pin "4-DIN") (pinfunction "DIN_4-DIN") (pintype "input"))
      (node (ref "LED54") (pin "2-DOUT") (pinfunction "DOUT_2-DOUT") (pintype "output"))
    )
    (net (code "34") (name "Net-(LED24-DOUT)") (class "Default")
      (node (ref "LED24") (pin "2-DOUT") (pinfunction "DOUT_2-DOUT") (pintype "output"))
      (node (ref "LED25") (pin "4-DIN") (pinfunction "DIN_4-DIN") (pintype "input"))
    )
    (net (code "35") (name "Net-(LED25-DOUT)") (class "Default")
      (node (ref "LED25") (pin "2-DOUT") (pinfunction "DOUT_2-DOUT") (pintype "output"))
      (node (ref "LED26") (pin "4-DIN") (pinfunction "DIN_4-DIN") (pintype "input"))
    )
    (net (code "36") (name "Net-(LED26-DOUT)") (class "Default")
      (node (ref "LED26") (pin "2-DOUT") (pinfunction "DOUT_2-DOUT") (pintype "output"))
      (node (ref "LED37") (pin "4-DIN") (pinfunction "DIN_4-DIN") (pintype "input"))
    )
    (net (code "37") (name "Net-(LED27-DOUT)") (class "Default")
      (node (ref "LED27") (pin "2-DOUT") (pinfunction "DOUT_2-DOUT") (pintype "output"))
      (node (ref "LED28") (pin "4-DIN") (pinfunction "DIN_4-DIN") (pintype "input"))
    )
    (net (code "38") (name "Net-(LED28-DOUT)") (class "Default")
      (node (ref "LED28") (pin "2-DOUT") (pinfunction "DOUT_2-DOUT") (pintype "output"))
      (node (ref "LED29") (pin "4-DIN") (pinfunction "DIN_4-DIN") (pintype "input"))
    )
    (net (code "39") (name "Net-(LED29-DOUT)") (class "Default")
      (node (ref "LED29") (pin "2-DOUT") (pinfunction "DOUT_2-DOUT") (pintype "output"))
      (node (ref "LED40") (pin "4-DIN") (pinfunction "DIN_4-DIN") (pintype "input"))
    )
    (net (code "40") (name "Net-(LED30-DIN)") (class "Default")
      (node (ref "LED30") (pin "4-DIN") (pinfunction "DIN_4-DIN") (pintype "input"))
      (node (ref "LED31") (pin "2-DOUT") (pinfunction "DOUT_2-DOUT") (pintype "output"))
    )
    (net (code "41") (name "Net-(LED30-DOUT)") (class "Default")
      (node (ref "LED30") (pin "2-DOUT") (pinfunction "DOUT_2-DOUT") (pintype "output"))
      (node (ref "LED53") (pin "4-DIN") (pinfunction "DIN_4-DIN") (pintype "input"))
    )
    (net (code "42") (name "Net-(LED31-DIN)") (class "Default")
      (node (ref "LED31") (pin "4-DIN") (pinfunction "DIN_4-DIN") (pintype "input"))
      (node (ref "LED43") (pin "2-DOUT") (pinfunction "DOUT_2-DOUT") (pintype "output"))
    )
    (net (code "43") (name "Net-(LED32-DOUT)") (class "Default")
      (node (ref "LED32") (pin "2-DOUT") (pinfunction "DOUT_2-DOUT") (pintype "output"))
      (node (ref "LED33") (pin "4-DIN") (pinfunction "DIN_4-DIN") (pintype "input"))
    )
    (net (code "44") (name "Net-(LED33-DOUT)") (class "Default")
      (node (ref "LED33") (pin "2-DOUT") (pinfunction "DOUT_2-DOUT") (pintype "output"))
      (node (ref "LED34") (pin "4-DIN") (pinfunction "DIN_4-DIN") (pintype "input"))
    )
    (net (code "45") (name "Net-(LED34-DOUT)") (class "Default")
      (node (ref "LED34") (pin "2-DOUT") (pinfunction "DOUT_2-DOUT") (pintype "output"))
      (node (ref "LED45") (pin "4-DIN") (pinfunction "DIN_4-DIN") (pintype "input"))
    )
    (net (code "46") (name "Net-(LED35-DIN)") (class "Default")
      (node (ref "LED35") (pin "4-DIN") (pinfunction "DIN_4-DIN") (pintype "input"))
      (node (ref "LED36") (pin "2-DOUT") (pinfunction "DOUT_2-DOUT") (pintype "output"))
    )
    (net (code "47") (name "Net-(LED35-DOUT)") (class "Default")
      (node (ref "LED35") (pin "2-DOUT") (pinfunction "DOUT_2-DOUT") (pintype "output"))
      (node (ref "LED54") (pin "4-DIN") (pinfunction "DIN_4-DIN") (pintype "input"))
    )
    (net (code "48") (name "Net-(LED36-DIN)") (class "Default")
      (node (ref "LED36") (pin "4-DIN") (pinfunction "DIN_4-DIN") (pintype "input"))
      (node (ref "LED48") (pin "2-DOUT") (pinfunction "DOUT_2-DOUT") (pintype "output"))
    )
    (net (code "49") (name "Net-(LED37-DOUT)") (class "Default")
      (node (ref "LED37") (pin "2-DOUT") (pinfunction "DOUT_2-DOUT") (pintype "output"))
      (node (ref "LED38") (pin "4-DIN") (pinfunction "DIN_4-DIN") (pintype "input"))
    )
    (net (code "50") (name "Net-(LED38-DOUT)") (class "Default")
      (node (ref "LED38") (pin "2-DOUT") (pinfunction "DOUT_2-DOUT") (pintype "output"))
      (node (ref "LED39") (pin "4-DIN") (pinfunction "DIN_4-DIN") (pintype "input"))
    )
    (net (code "51") (name "Net-(LED39-DOUT)") (class "Default")
      (node (ref "LED39") (pin "2-DOUT") (pinfunction "DOUT_2-DOUT") (pintype "output"))
      (node (ref "LED50") (pin "4-DIN") (pinfunction "DIN_4-DIN") (pintype "input"))
    )
    (net (code "52") (name "Net-(LED40-DOUT)") (class "Default")
      (node (ref "LED40") (pin "2-DOUT") (pinfunction "DOUT_2-DOUT") (pintype "output"))
      (node (ref "LED41") (pin "4-DIN") (pinfunction "DIN_4-DIN") (pintype "input"))
    )
    (net (code "53") (name "Net-(LED41-DOUT)") (class "Default")
      (node (ref "LED41") (pin "2-DOUT") (pinfunction "DOUT_2-DOUT") (pintype "output"))
      (node (ref "LED42") (pin "4-DIN") (pinfunction "DIN_4-DIN") (pintype "input"))
    )
    (net (code "54") (name "Net-(LED42-DOUT)") (class "Default")
      (node (ref "LED42") (pin "2-DOUT") (pinfunction "DOUT_2-DOUT") (pintype "output"))
      (node (ref "LED44") (pin "4-DIN") (pinfunction "DIN_4-DIN") (pintype "input"))
    )
    (net (code "55") (name "Net-(LED43-DIN)") (class "Default")
      (node (ref "LED43") (pin "4-DIN") (pinfunction "DIN_4-DIN") (pintype "input"))
      (node (ref "LED44") (pin "2-DOUT") (pinfunction "DOUT_2-DOUT") (pintype "output"))
    )
    (net (code "56") (name "Net-(LED45-DOUT)") (class "Default")
      (node (ref "LED45") (pin "2-DOUT") (pinfunction "DOUT_2-DOUT") (pintype "output"))
      (node (ref "LED46") (pin "4-DIN") (pinfunction "DIN_4-DIN") (pintype "input"))
    )
    (net (code "57") (name "Net-(LED46-DOUT)") (class "Default")
      (node (ref "LED46") (pin "2-DOUT") (pinfunction "DOUT_2-DOUT") (pintype "output"))
      (node (ref "LED47") (pin "4-DIN") (pinfunction "DIN_4-DIN") (pintype "input"))
    )
    (net (code "58") (name "Net-(LED47-DOUT)") (class "Default")
      (node (ref "LED47") (pin "2-DOUT") (pinfunction "DOUT_2-DOUT") (pintype "output"))
      (node (ref "LED49") (pin "4-DIN") (pinfunction "DIN_4-DIN") (pintype "input"))
    )
    (net (code "59") (name "Net-(LED48-DIN)") (class "Default")
      (node (ref "LED48") (pin "4-DIN") (pinfunction "DIN_4-DIN") (pintype "input"))
      (node (ref "LED49") (pin "2-DOUT") (pinfunction "DOUT_2-DOUT") (pintype "output"))
    )
    (net (code "60") (name "Net-(LED50-DOUT)") (class "Default")
      (node (ref "LED50") (pin "2-DOUT") (pinfunction "DOUT_2-DOUT") (pintype "output"))
      (node (ref "LED51") (pin "4-DIN") (pinfunction "DIN_4-DIN") (pintype "input"))
    )
    (net (code "61") (name "Net-(LED51-DOUT)") (class "Default")
      (node (ref "LED51") (pin "2-DOUT") (pinfunction "DOUT_2-DOUT") (pintype "output"))
      (node (ref "LED52") (pin "4-DIN") (pinfunction "DIN_4-DIN") (pintype "input"))
    )
    (net (code "62") (name "VDD") (class "Default")
      (node (ref "C1") (pin "1") (pinfunction "1_1") (pintype "passive"))
      (node (ref "C10") (pin "1") (pinfunction "1_1") (pintype "passive"))
      (node (ref "C11") (pin "1") (pinfunction "1_1") (pintype "passive"))
      (node (ref "C12") (pin "1") (pinfunction "1_1") (pintype "passive"))
      (node (ref "C13") (pin "1") (pinfunction "1_1") (pintype "passive"))
      (node (ref "C14") (pin "1") (pinfunction "1_1") (pintype "passive"))
      (node (ref "C15") (pin "1") (pinfunction "1_1") (pintype "passive"))
      (node (ref "C16") (pin "1") (pinfunction "1_1") (pintype "passive"))
      (node (ref "C17") (pin "1") (pinfunction "1_1") (pintype "passive"))
      (node (ref "C18") (pin "1") (pinfunction "1_1") (pintype "passive"))
      (node (ref "C19") (pin "1") (pinfunction "1_1") (pintype "passive"))
      (node (ref "C2") (pin "1") (pinfunction "1_1") (pintype "passive"))
      (node (ref "C20") (pin "1") (pinfunction "1_1") (pintype "passive"))
      (node (ref "C21") (pin "1") (pinfunction "1_1") (pintype "passive"))
      (node (ref "C22") (pin "1") (pinfunction "1_1") (pintype "passive"))
      (node (ref "C23") (pin "1") (pinfunction "1_1") (pintype "passive"))
      (node (ref "C24") (pin "1") (pinfunction "1_1") (pintype "passive"))
      (node (ref "C25") (pin "1") (pinfunction "1_1") (pintype "passive"))
      (node (ref "C26") (pin "1") (pinfunction "1_1") (pintype "passive"))
      (node (ref "C27") (pin "1") (pinfunction "1_1") (pintype "passive"))
      (node (ref "C28") (pin "1") (pinfunction "1_1") (pintype "passive"))
      (node (ref "C29") (pin "1") (pinfunction "1_1") (pintype "passive"))
      (node (ref "C3") (pin "1") (pinfunction "1_1") (pintype "passive"))
      (node (ref "C30") (pin "1") (pinfunction "1_1") (pintype "passive"))
      (node (ref "C31") (pin "1") (pinfunction "1_1") (pintype "passive"))
      (node (ref "C32") (pin "1") (pinfunction "1_1") (pintype "passive"))
      (node (ref "C33") (pin "1") (pinfunction "1_1") (pintype "passive"))
      (node (ref "C34") (pin "1") (pinfunction "1_1") (pintype "passive"))
      (node (ref "C35") (pin "1") (pinfunction "1_1") (pintype "passive"))
      (node (ref "C36") (pin "1") (pinfunction "1_1") (pintype "passive"))
      (node (ref "C37") (pin "1") (pinfunction "1_1") (pintype "passive"))
      (node (ref "C38") (pin "1") (pinfunction "1_1") (pintype "passive"))
      (node (ref "C39") (pin "1") (pinfunction "1_1") (pintype "passive"))
      (node (ref "C4") (pin "1") (pinfunction "1_1") (pintype "passive"))
      (node (ref "C400") (pin "+") (pinfunction "+_+") (pintype "passive"))
      (node (ref "C401") (pin "+") (pinfunction "+_+") (pintype "passive"))
      (node (ref "C41") (pin "1") (pinfunction "1_1") (pintype "passive"))
      (node (ref "C42") (pin "1") (pinfunction "1_1") (pintype "passive"))
      (node (ref "C43") (pin "1") (pinfunction "1_1") (pintype "passive"))
      (node (ref "C44") (pin "1") (pinfunction "1_1") (pintype "passive"))
      (node (ref "C45") (pin "1") (pinfunction "1_1") (pintype "passive"))
      (node (ref "C46") (pin "1") (pinfunction "1_1") (pintype "passive"))
      (node (ref "C47") (pin "1") (pinfunction "1_1") (pintype "passive"))
      (node (ref "C48") (pin "1") (pinfunction "1_1") (pintype "passive"))
      (node (ref "C49") (pin "1") (pinfunction "1_1") (pintype "passive"))
      (node (ref "C5") (pin "1") (pinfunction "1_1") (pintype "passive"))
      (node (ref "C50") (pin "1") (pinfunction "1_1") (pintype "passive"))
      (node (ref "C51") (pin "1") (pinfunction "1_1") (pintype "passive"))
      (node (ref "C52") (pin "1") (pinfunction "1_1") (pintype "passive"))
      (node (ref "C53") (pin "1") (pinfunction "1_1") (pintype "passive"))
      (node (ref "C54") (pin "1") (pinfunction "1_1") (pintype "passive"))
      (node (ref "C6") (pin "1") (pinfunction "1_1") (pintype "passive"))
      (node (ref "C7") (pin "1") (pinfunction "1_1") (pintype "passive"))
      (node (ref "C8") (pin "1") (pinfunction "1_1") (pintype "passive"))
      (node (ref "C9") (pin "1") (pinfunction "1_1") (pintype "passive"))
      (node (ref "J1") (pin "1") (pinfunction "1_1") (pintype "passive"))
      (node (ref "JP2") (pin "VBUS") (pinfunction "VBUS_VBUS") (pintype "bidirectional"))
      (node (ref "LED1") (pin "1-VDD") (pinfunction "VDD_1-VDD") (pintype "bidirectional"))
      (node (ref "LED10") (pin "1-VDD") (pinfunction "VDD_1-VDD") (pintype "bidirectional"))
      (node (ref "LED11") (pin "1-VDD") (pinfunction "VDD_1-VDD") (pintype "bidirectional"))
      (node (ref "LED12") (pin "1-VDD") (pinfunction "VDD_1-VDD") (pintype "bidirectional"))
      (node (ref "LED13") (pin "1-VDD") (pinfunction "VDD_1-VDD") (pintype "bidirectional"))
      (node (ref "LED14") (pin "1-VDD") (pinfunction "VDD_1-VDD") (pintype "bidirectional"))
      (node (ref "LED15") (pin "1-VDD") (pinfunction "VDD_1-VDD") (pintype "bidirectional"))
      (node (ref "LED16") (pin "1-VDD") (pinfunction "VDD_1-VDD") (pintype "bidirectional"))
      (node (ref "LED17") (pin "1-VDD") (pinfunction "VDD_1-VDD") (pintype "bidirectional"))
      (node (ref "LED18") (pin "1-VDD") (pinfunction "VDD_1-VDD") (pintype "bidirectional"))
      (node (ref "LED19") (pin "1-VDD") (pinfunction "VDD_1-VDD") (pintype "bidirectional"))
      (node (ref "LED2") (pin "1-VDD") (pinfunction "VDD_1-VDD") (pintype "bidirectional"))
      (node (ref "LED20") (pin "1-VDD") (pinfunction "VDD_1-VDD") (pintype "bidirectional"))
      (node (ref "LED21") (pin "1-VDD") (pinfunction "VDD_1-VDD") (pintype "bidirectional"))
      (node (ref "LED22") (pin "1-VDD") (pinfunction "VDD_1-VDD") (pintype "bidirectional"))
      (node (ref "LED23") (pin "1-VDD") (pinfunction "VDD_1-VDD") (pintype "bidirectional"))
      (node (ref "LED24") (pin "1-VDD") (pinfunction "VDD_1-VDD") (pintype "bidirectional"))
      (node (ref "LED25") (pin "1-VDD") (pinfunction "VDD_1-VDD") (pintype "bidirectional"))
      (node (ref "LED26") (pin "1-VDD") (pinfunction "VDD_1-VDD") (pintype "bidirectional"))
      (node (ref "LED27") (pin "1-VDD") (pinfunction "VDD_1-VDD") (pintype "bidirectional"))
      (node (ref "LED28") (pin "1-VDD") (pinfunction "VDD_1-VDD") (pintype "bidirectional"))
      (node (ref "LED29") (pin "1-VDD") (pinfunction "VDD_1-VDD") (pintype "bidirectional"))
      (node (ref "LED3") (pin "1-VDD") (pinfunction "VDD_1-VDD") (pintype "bidirectional"))
      (node (ref "LED30") (pin "1-VDD") (pinfunction "VDD_1-VDD") (pintype "bidirectional"))
      (node (ref "LED31") (pin "1-VDD") (pinfunction "VDD_1-VDD") (pintype "bidirectional"))
      (node (ref "LED32") (pin "1-VDD") (pinfunction "VDD_1-VDD") (pintype "bidirectional"))
      (node (ref "LED33") (pin "1-VDD") (pinfunction "VDD_1-VDD") (pintype "bidirectional"))
      (node (ref "LED34") (pin "1-VDD") (pinfunction "VDD_1-VDD") (pintype "bidirectional"))
      (node (ref "LED35") (pin "1-VDD") (pinfunction "VDD_1-VDD") (pintype "bidirectional"))
      (node (ref "LED36") (pin "1-VDD") (pinfunction "VDD_1-VDD") (pintype "bidirectional"))
      (node (ref "LED37") (pin "1-VDD") (pinfunction "VDD_1-VDD") (pintype "bidirectional"))
      (node (ref "LED38") (pin "1-VDD") (pinfunction "VDD_1-VDD") (pintype "bidirectional"))
      (node (ref "LED39") (pin "1-VDD") (pinfunction "VDD_1-VDD") (pintype "bidirectional"))
      (node (ref "LED4") (pin "1-VDD") (pinfunction "VDD_1-VDD") (pintype "bidirectional"))
      (node (ref "LED40") (pin "1-VDD") (pinfunction "VDD_1-VDD") (pintype "bidirectional"))
      (node (ref "LED41") (pin "1-VDD") (pinfunction "VDD_1-VDD") (pintype "bidirectional"))
      (node (ref "LED42") (pin "1-VDD") (pinfunction "VDD_1-VDD") (pintype "bidirectional"))
      (node (ref "LED43") (pin "1-VDD") (pinfunction "VDD_1-VDD") (pintype "bidirectional"))
      (node (ref "LED44") (pin "1-VDD") (pinfunction "VDD_1-VDD") (pintype "bidirectional"))
      (node (ref "LED45") (pin "1-VDD") (pinfunction "VDD_1-VDD") (pintype "bidirectional"))
      (node (ref "LED46") (pin "1-VDD") (pinfunction "VDD_1-VDD") (pintype "bidirectional"))
      (node (ref "LED47") (pin "1-VDD") (pinfunction "VDD_1-VDD") (pintype "bidirectional"))
      (node (ref "LED48") (pin "1-VDD") (pinfunction "VDD_1-VDD") (pintype "bidirectional"))
      (node (ref "LED49") (pin "1-VDD") (pinfunction "VDD_1-VDD") (pintype "bidirectional"))
      (node (ref "LED5") (pin "1-VDD") (pinfunction "VDD_1-VDD") (pintype "bidirectional"))
      (node (ref "LED50") (pin "1-VDD") (pinfunction "VDD_1-VDD") (pintype "bidirectional"))
      (node (ref "LED51") (pin "1-VDD") (pinfunction "VDD_1-VDD") (pintype "bidirectional"))
      (node (ref "LED52") (pin "1-VDD") (pinfunction "VDD_1-VDD") (pintype "bidirectional"))
      (node (ref "LED53") (pin "1-VDD") (pinfunction "VDD_1-VDD") (pintype "bidirectional"))
      (node (ref "LED54") (pin "1-VDD") (pinfunction "VDD_1-VDD") (pintype "bidirectional"))
      (node (ref "LED6") (pin "1-VDD") (pinfunction "VDD_1-VDD") (pintype "bidirectional"))
      (node (ref "LED7") (pin "1-VDD") (pinfunction "VDD_1-VDD") (pintype "bidirectional"))
      (node (ref "LED8") (pin "1-VDD") (pinfunction "VDD_1-VDD") (pintype "bidirectional"))
      (node (ref "LED9") (pin "1-VDD") (pinfunction "VDD_1-VDD") (pintype "bidirectional"))
    )
    (net (code "63") (name "VIN") (class "Default")
      (node (ref "U$1") (pin "VIN") (pinfunction "VIN_VIN") (pintype "power_in"))
    )
    (net (code "64") (name "unconnected-(JP2-PadD+)") (class "Default")
      (node (ref "JP2") (pin "D+") (pinfunction "D+_D+") (pintype "bidirectional"))
    )
    (net (code "65") (name "unconnected-(JP2-PadD-)") (class "Default")
      (node (ref "JP2") (pin "D-") (pinfunction "D-_D-") (pintype "bidirectional"))
    )
    (net (code "66") (name "unconnected-(LED52-DOUT-Pad2-DOUT)") (class "Default")
      (node (ref "LED52") (pin "2-DOUT") (pinfunction "DOUT_2-DOUT") (pintype "output"))
    )
    (net (code "67") (name "unconnected-(U$1-PadA0)") (class "Default")
      (node (ref "U$1") (pin "A0") (pinfunction "A0_A0") (pintype "bidirectional"))
    )
    (net (code "68") (name "unconnected-(U$1-PadA1)") (class "Default")
      (node (ref "U$1") (pin "A1") (pinfunction "A1_A1") (pintype "bidirectional"))
    )
    (net (code "69") (name "unconnected-(U$1-PadA2)") (class "Default")
      (node (ref "U$1") (pin "A2") (pinfunction "A2_A2") (pintype "bidirectional"))
    )
    (net (code "70") (name "unconnected-(U$1-PadA3)") (class "Default")
      (node (ref "U$1") (pin "A3") (pinfunction "A3_A3") (pintype "bidirectional"))
    )
    (net (code "71") (name "unconnected-(U$1-PadA4)") (class "Default")
      (node (ref "U$1") (pin "A4") (pinfunction "A4_A4") (pintype "bidirectional"))
    )
    (net (code "72") (name "unconnected-(U$1-PadA5)") (class "Default")
      (node (ref "U$1") (pin "A5") (pinfunction "A5_A5") (pintype "bidirectional"))
    )
    (net (code "73") (name "unconnected-(U$1-PadAREF)") (class "Default")
      (node (ref "U$1") (pin "AREF") (pinfunction "AREF_AREF") (pintype "bidirectional"))
    )
    (net (code "74") (name "unconnected-(U$1-PadD1)") (class "Default")
      (node (ref "U$1") (pin "D1") (pinfunction "D1_D1") (pintype "bidirectional"))
    )
    (net (code "75") (name "unconnected-(U$1-PadD2)") (class "Default")
      (node (ref "U$1") (pin "D2") (pinfunction "D2_D2") (pintype "bidirectional"))
    )
    (net (code "76") (name "unconnected-(U$1-PadD3)") (class "Default")
      (node (ref "U$1") (pin "D3") (pinfunction "D3_D3") (pintype "bidirectional"))
    )
    (net (code "77") (name "unconnected-(U$1-PadD4)") (class "Default")
      (node (ref "U$1") (pin "D4") (pinfunction "D4_D4") (pintype "bidirectional"))
    )
    (net (code "78") (name "unconnected-(U$1-PadD5)") (class "Default")
      (node (ref "U$1") (pin "D5") (pinfunction "D5_D5") (pintype "bidirectional"))
    )
    (net (code "79") (name "unconnected-(U$1-PadD6)") (class "Default")
      (node (ref "U$1") (pin "D6") (pinfunction "D6_D6") (pintype "bidirectional"))
    )
    (net (code "80") (name "unconnected-(U$1-PadD7)") (class "Default")
      (node (ref "U$1") (pin "D7") (pinfunction "D7_D7") (pintype "bidirectional"))
    )
    (net (code "81") (name "unconnected-(U$1-PadD8)") (class "Default")
      (node (ref "U$1") (pin "D8") (pinfunction "D8_D8") (pintype "bidirectional"))
    )
    (net (code "82") (name "unconnected-(U$1-PadD9)") (class "Default")
      (node (ref "U$1") (pin "D9") (pinfunction "D9_D9") (pintype "bidirectional"))
    )
    (net (code "83") (name "unconnected-(U$1-PadD10)") (class "Default")
      (node (ref "U$1") (pin "D10") (pinfunction "D10_D10") (pintype "bidirectional"))
    )
    (net (code "84") (name "unconnected-(U$1-{slash}RESET-PadRESET)") (class "Default")
      (node (ref "U$1") (pin "RESET") (pinfunction "/RESET_RESET") (pintype "bidirectional"))
    )
  )
)
